# UIO_Int.net
KiCad netlist of a schematic drawn in Altium Designer
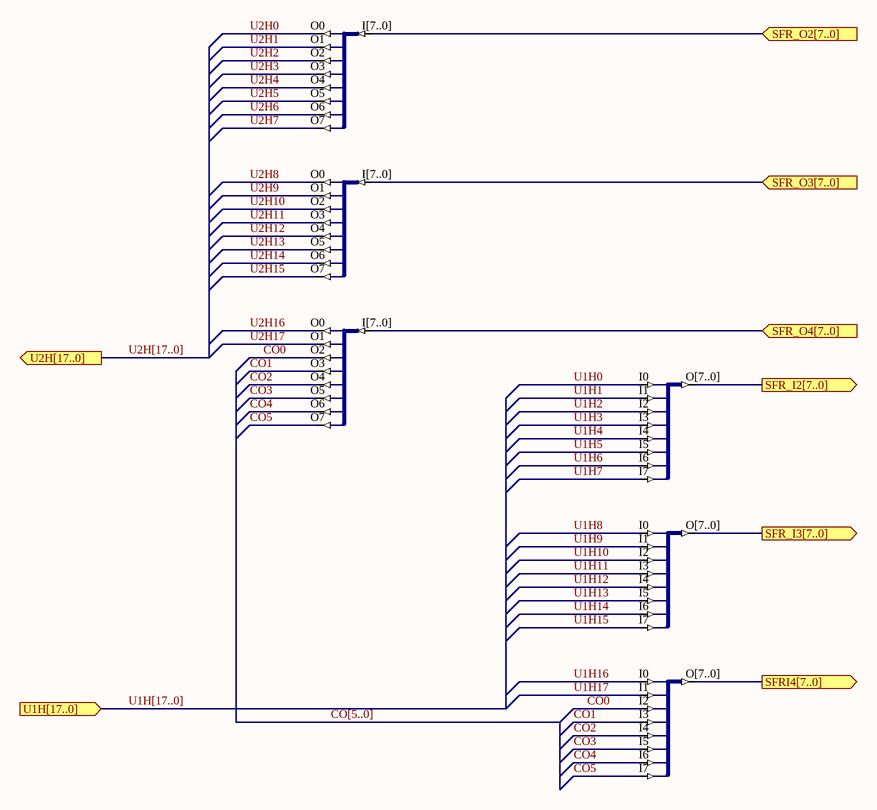
[diagram p0: UIO_Int.SchDoc]

(export (version "E")
  (design (tool "Eeschema 10.0.6"))
  (components
    (comp (ref "U1")
      (value "J8B_8S")
      (description "8-Bit input bus to 8 single pin outputs")
      (fields (field (name "PUBLISHER") "Altium Limited"))
      (libsource (lib "FPGA Generic") (part "J8B_8S"))
    )
    (comp (ref "U2")
      (value "J8B_8S")
      (description "8-Bit input bus to 8 single pin outputs")
      (fields (field (name "PUBLISHER") "Altium Limited"))
      (libsource (lib "FPGA Generic") (part "J8B_8S"))
    )
    (comp (ref "U3")
      (value "J8B_8S")
      (description "8-Bit input bus to 8 single pin outputs")
      (fields (field (name "PUBLISHER") "Altium Limited"))
      (libsource (lib "FPGA Generic") (part "J8B_8S"))
    )
    (comp (ref "U4")
      (value "J8S_8B")
      (description "8 Single pin inputs to single 8-Bit output bus")
      (fields (field (name "PUBLISHER") "Altium Limited"))
      (libsource (lib "FPGA Generic") (part "J8S_8B"))
    )
    (comp (ref "U5")
      (value "J8S_8B")
      (description "8 Single pin inputs to single 8-Bit output bus")
      (fields (field (name "PUBLISHER") "Altium Limited"))
      (libsource (lib "FPGA Generic") (part "J8S_8B"))
    )
    (comp (ref "U6")
      (value "J8S_8B")
      (description "8 Single pin inputs to single 8-Bit output bus")
      (fields (field (name "PUBLISHER") "Altium Limited"))
      (libsource (lib "FPGA Generic") (part "J8S_8B"))
    )
  )
  (nets
    (net (code "49") (name "/CO0") (class "Default")
      (node (ref "U3") (pin "O2") (pinfunction "O2_O2") (pintype "output"))
      (node (ref "U6") (pin "I2") (pinfunction "I2_I2") (pintype "input"))
    )
    (net (code "50") (name "/CO1") (class "Default")
      (node (ref "U3") (pin "O3") (pinfunction "O3_O3") (pintype "output"))
      (node (ref "U6") (pin "I3") (pinfunction "I3_I3") (pintype "input"))
    )
    (net (code "51") (name "/CO2") (class "Default")
      (node (ref "U3") (pin "O4") (pinfunction "O4_O4") (pintype "output"))
      (node (ref "U6") (pin "I4") (pinfunction "I4_I4") (pintype "input"))
    )
    (net (code "52") (name "/CO3") (class "Default")
      (node (ref "U3") (pin "O5") (pinfunction "O5_O5") (pintype "output"))
      (node (ref "U6") (pin "I5") (pinfunction "I5_I5") (pintype "input"))
    )
    (net (code "53") (name "/CO4") (class "Default")
      (node (ref "U3") (pin "O6") (pinfunction "O6_O6") (pintype "output"))
      (node (ref "U6") (pin "I6") (pinfunction "I6_I6") (pintype "input"))
    )
    (net (code "54") (name "/CO5") (class "Default")
      (node (ref "U3") (pin "O7") (pinfunction "O7_O7") (pintype "output"))
      (node (ref "U6") (pin "I7") (pinfunction "I7_I7") (pintype "input"))
    )
    (net (code "56") (name "/SFRI4[7..0]") (class "Default")
      (node (ref "U6") (pin "O[7..0]") (pinfunction "O[7..0]_O[7..0]") (pintype "output"))
    )
    (net (code "57") (name "/SFR_I2[7..0]") (class "Default")
      (node (ref "U4") (pin "O[7..0]") (pinfunction "O[7..0]_O[7..0]") (pintype "output"))
    )
    (net (code "58") (name "/SFR_I3[7..0]") (class "Default")
      (node (ref "U5") (pin "O[7..0]") (pinfunction "O[7..0]_O[7..0]") (pintype "output"))
    )
    (net (code "59") (name "/SFR_O2[7..0]") (class "Default")
      (node (ref "U1") (pin "I[7..0]") (pinfunction "I[7..0]_I[7..0]") (pintype "input"))
    )
    (net (code "60") (name "/SFR_O3[7..0]") (class "Default")
      (node (ref "U2") (pin "I[7..0]") (pinfunction "I[7..0]_I[7..0]") (pintype "input"))
    )
    (net (code "61") (name "/SFR_O4[7..0]") (class "Default")
      (node (ref "U3") (pin "I[7..0]") (pinfunction "I[7..0]_I[7..0]") (pintype "input"))
    )
    (net (code "62") (name "/U1H0") (class "Default")
      (node (ref "U4") (pin "I0") (pinfunction "I0_I0") (pintype "input"))
    )
    (net (code "63") (name "/U1H1") (class "Default")
      (node (ref "U4") (pin "I1") (pinfunction "I1_I1") (pintype "input"))
    )
    (net (code "64") (name "/U1H2") (class "Default")
      (node (ref "U4") (pin "I2") (pinfunction "I2_I2") (pintype "input"))
    )
    (net (code "65") (name "/U1H3") (class "Default")
      (node (ref "U4") (pin "I3") (pinfunction "I3_I3") (pintype "input"))
    )
    (net (code "66") (name "/U1H4") (class "Default")
      (node (ref "U4") (pin "I4") (pinfunction "I4_I4") (pintype "input"))
    )
    (net (code "67") (name "/U1H5") (class "Default")
      (node (ref "U4") (pin "I5") (pinfunction "I5_I5") (pintype "input"))
    )
    (net (code "68") (name "/U1H6") (class "Default")
      (node (ref "U4") (pin "I6") (pinfunction "I6_I6") (pintype "input"))
    )
    (net (code "69") (name "/U1H7") (class "Default")
      (node (ref "U4") (pin "I7") (pinfunction "I7_I7") (pintype "input"))
    )
    (net (code "70") (name "/U1H8") (class "Default")
      (node (ref "U5") (pin "I0") (pinfunction "I0_I0") (pintype "input"))
    )
    (net (code "71") (name "/U1H9") (class "Default")
      (node (ref "U5") (pin "I1") (pinfunction "I1_I1") (pintype "input"))
    )
    (net (code "72") (name "/U1H10") (class "Default")
      (node (ref "U5") (pin "I2") (pinfunction "I2_I2") (pintype "input"))
    )
    (net (code "73") (name "/U1H11") (class "Default")
      (node (ref "U5") (pin "I3") (pinfunction "I3_I3") (pintype "input"))
    )
    (net (code "74") (name "/U1H12") (class "Default")
      (node (ref "U5") (pin "I4") (pinfunction "I4_I4") (pintype "input"))
    )
    (net (code "75") (name "/U1H13") (class "Default")
      (node (ref "U5") (pin "I5") (pinfunction "I5_I5") (pintype "input"))
    )
    (net (code "76") (name "/U1H14") (class "Default")
      (node (ref "U5") (pin "I6") (pinfunction "I6_I6") (pintype "input"))
    )
    (net (code "77") (name "/U1H15") (class "Default")
      (node (ref "U5") (pin "I7") (pinfunction "I7_I7") (pintype "input"))
    )
    (net (code "78") (name "/U1H16") (class "Default")
      (node (ref "U6") (pin "I0") (pinfunction "I0_I0") (pintype "input"))
    )
    (net (code "79") (name "/U1H17") (class "Default")
      (node (ref "U6") (pin "I1") (pinfunction "I1_I1") (pintype "input"))
    )
    (net (code "81") (name "/U2H0") (class "Default")
      (node (ref "U1") (pin "O0") (pinfunction "O0_O0") (pintype "output"))
    )
    (net (code "82") (name "/U2H1") (class "Default")
      (node (ref "U1") (pin "O1") (pinfunction "O1_O1") (pintype "output"))
    )
    (net (code "83") (name "/U2H2") (class "Default")
      (node (ref "U1") (pin "O2") (pinfunction "O2_O2") (pintype "output"))
    )
    (net (code "84") (name "/U2H3") (class "Default")
      (node (ref "U1") (pin "O3") (pinfunction "O3_O3") (pintype "output"))
    )
    (net (code "85") (name "/U2H4") (class "Default")
      (node (ref "U1") (pin "O4") (pinfunction "O4_O4") (pintype "output"))
    )
    (net (code "86") (name "/U2H5") (class "Default")
      (node (ref "U1") (pin "O5") (pinfunction "O5_O5") (pintype "output"))
    )
    (net (code "87") (name "/U2H6") (class "Default")
      (node (ref "U1") (pin "O6") (pinfunction "O6_O6") (pintype "output"))
    )
    (net (code "88") (name "/U2H7") (class "Default")
      (node (ref "U1") (pin "O7") (pinfunction "O7_O7") (pintype "output"))
    )
    (net (code "89") (name "/U2H8") (class "Default")
      (node (ref "U2") (pin "O0") (pinfunction "O0_O0") (pintype "output"))
    )
    (net (code "90") (name "/U2H9") (class "Default")
      (node (ref "U2") (pin "O1") (pinfunction "O1_O1") (pintype "output"))
    )
    (net (code "91") (name "/U2H10") (class "Default")
      (node (ref "U2") (pin "O2") (pinfunction "O2_O2") (pintype "output"))
    )
    (net (code "92") (name "/U2H11") (class "Default")
      (node (ref "U2") (pin "O3") (pinfunction "O3_O3") (pintype "output"))
    )
    (net (code "93") (name "/U2H12") (class "Default")
      (node (ref "U2") (pin "O4") (pinfunction "O4_O4") (pintype "output"))
    )
    (net (code "94") (name "/U2H13") (class "Default")
      (node (ref "U2") (pin "O5") (pinfunction "O5_O5") (pintype "output"))
    )
    (net (code "95") (name "/U2H14") (class "Default")
      (node (ref "U2") (pin "O6") (pinfunction "O6_O6") (pintype "output"))
    )
    (net (code "96") (name "/U2H15") (class "Default")
      (node (ref "U2") (pin "O7") (pinfunction "O7_O7") (pintype "output"))
    )
    (net (code "97") (name "/U2H16") (class "Default")
      (node (ref "U3") (pin "O0") (pinfunction "O0_O0") (pintype "output"))
    )
    (net (code "98") (name "/U2H17") (class "Default")
      (node (ref "U3") (pin "O1") (pinfunction "O1_O1") (pintype "output"))
    )
  )
)
